# Sheet2.net
KiCad netlist of a schematic drawn in Altium Designer
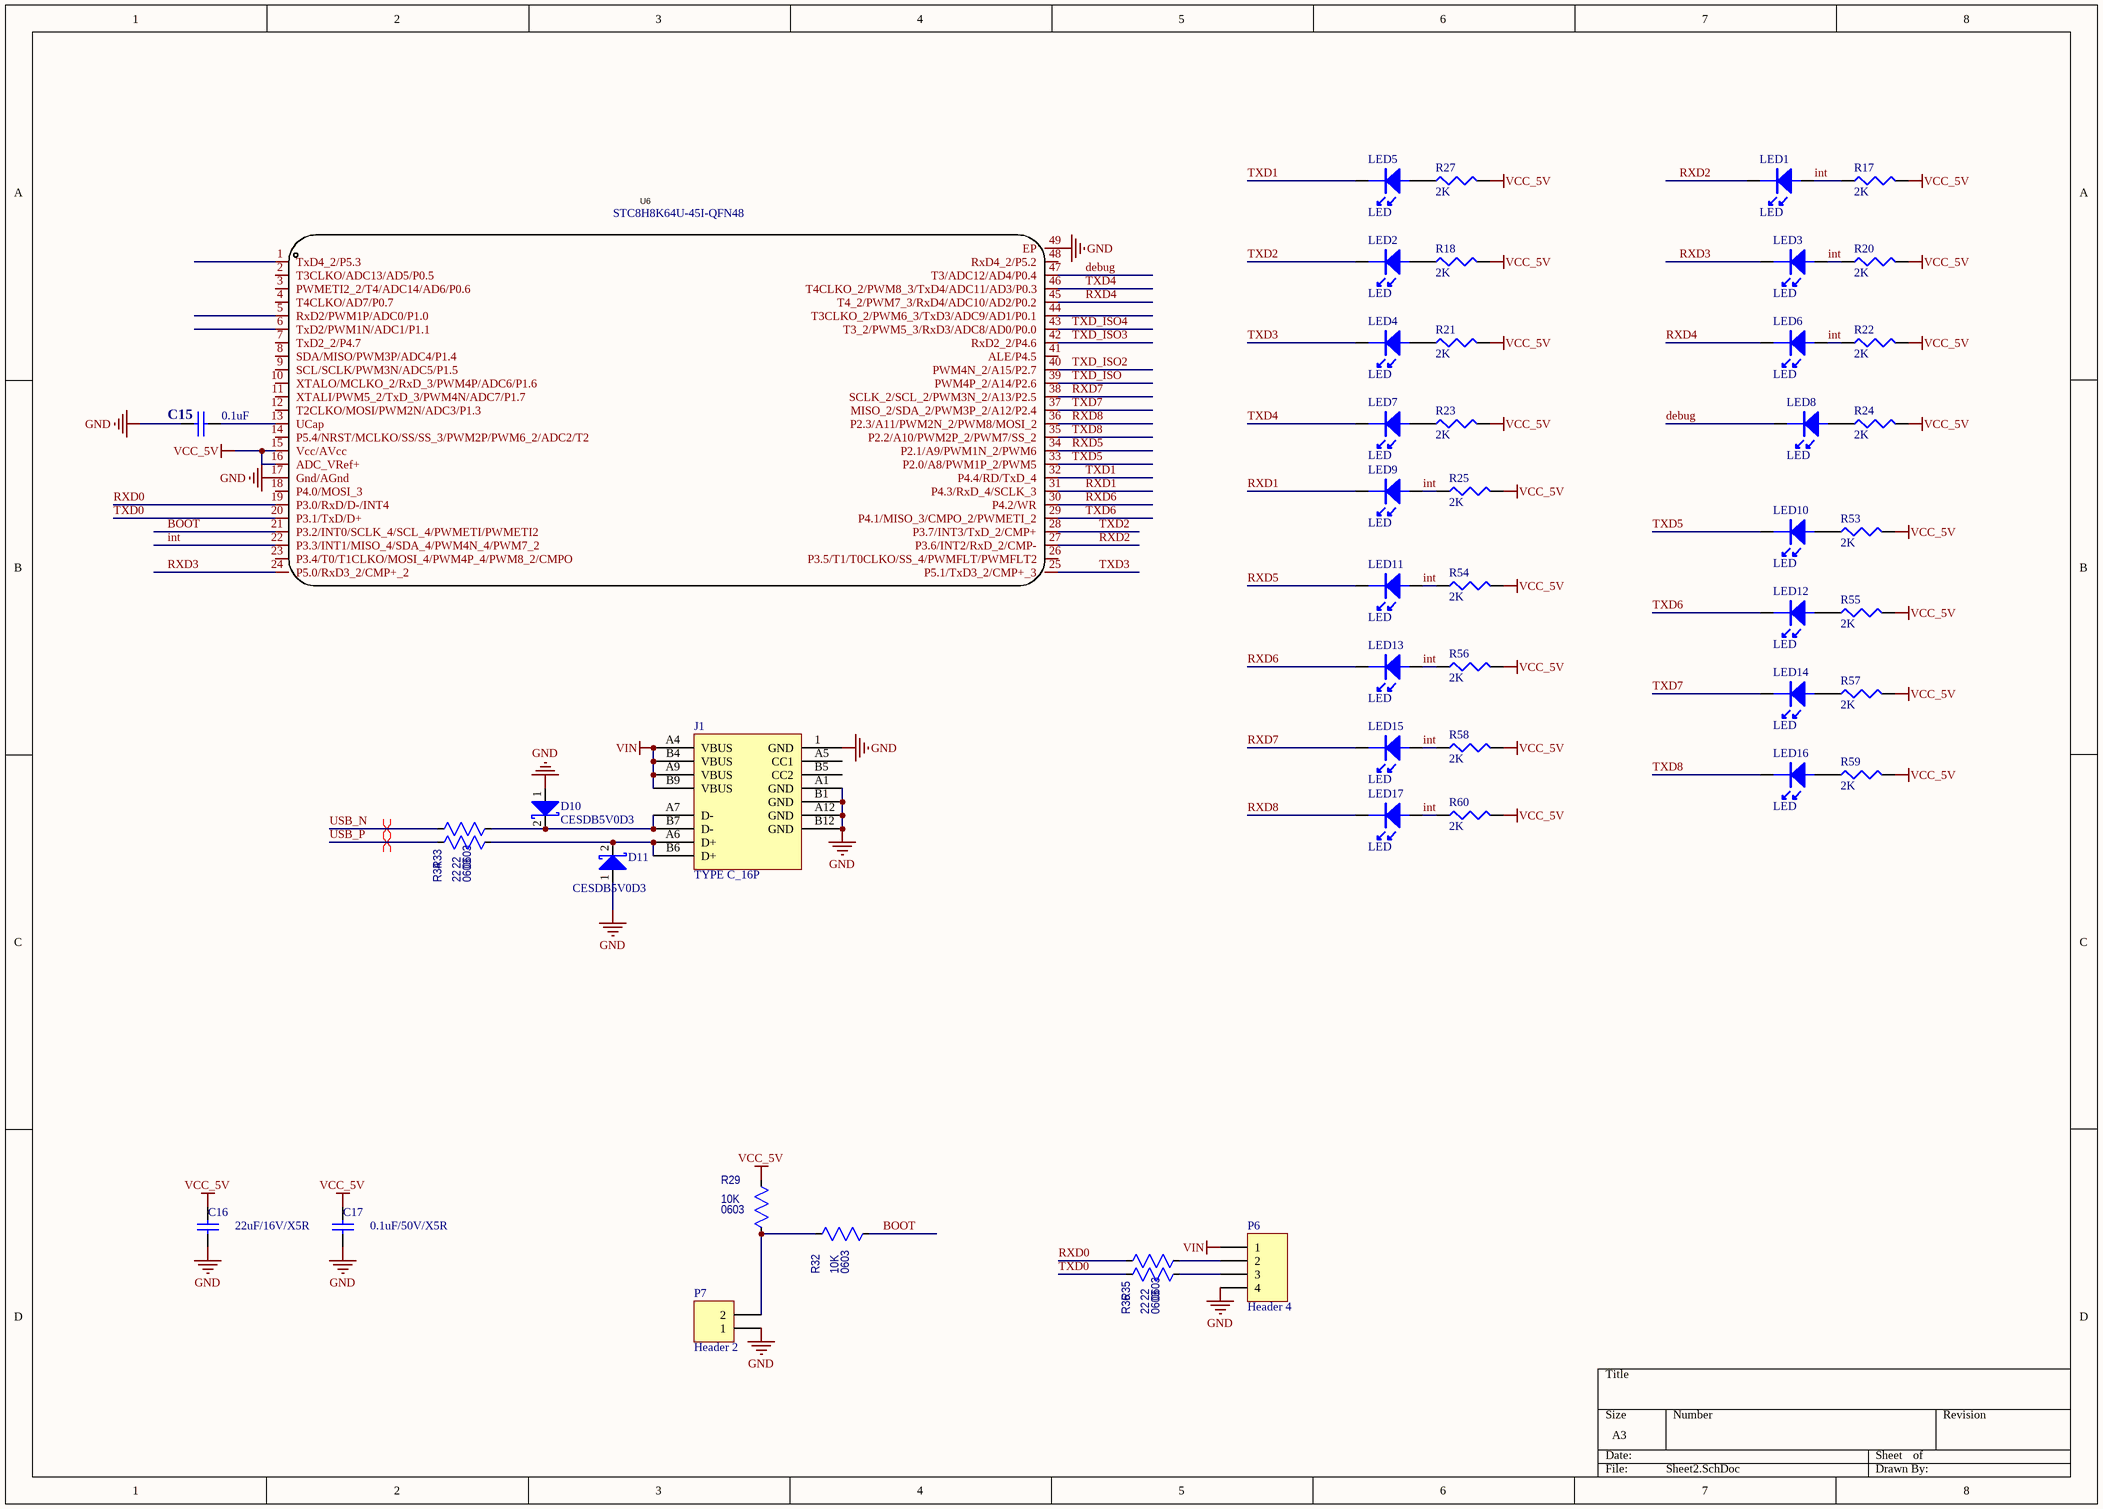
[diagram p0: Sheet2.SchDoc]

(export (version "E")
  (design (tool "Eeschema 10.0.6"))
  (components
    (comp (ref "C15")
      (value "0.1uF")
      (footprint "0603C")
      (description "Capacitor")
      (libsource (lib "*") (part "CAP"))
    )
    (comp (ref "C16")
      (value "22uF/16V/X5R")
      (footprint "0805C")
      (description "贴片电容 20%")
      (libsource (lib "XiaoyI") (part "CAP4"))
    )
    (comp (ref "C17")
      (value "0.1uF/50V/X5R")
      (footprint "0603C")
      (description "贴片电容 20%")
      (libsource (lib "XiaoyI") (part "CAP4"))
    )
    (comp (ref "D10")
      (value "CESDB5V0D3")
      (footprint "SOD323")
      (description "Schottky Diode")
      (libsource (lib "*") (part "DIODE S"))
    )
    (comp (ref "D11")
      (value "CESDB5V0D3")
      (footprint "SOD323")
      (description "Schottky Diode")
      (libsource (lib "*") (part "DIODE S"))
    )
    (comp (ref "J1")
      (value "TYPE C_16P")
      (footprint "TYPEC_16P")
      (libsource (lib "Schlib_20110825") (part "TYPE C_16P"))
    )
    (comp (ref "LED1") (value "LED") (footprint "0603LED") (libsource (lib "我的元件库") (part "LED")))
    (comp (ref "LED2") (value "LED") (footprint "0603LED") (libsource (lib "我的元件库") (part "LED")))
    (comp (ref "LED3") (value "LED") (footprint "0603LED") (libsource (lib "我的元件库") (part "LED")))
    (comp (ref "LED4") (value "LED") (footprint "0603LED") (libsource (lib "我的元件库") (part "LED")))
    (comp (ref "LED5") (value "LED") (footprint "0603LED") (libsource (lib "我的元件库") (part "LED")))
    (comp (ref "LED6") (value "LED") (footprint "0603LED") (libsource (lib "我的元件库") (part "LED")))
    (comp (ref "LED7") (value "LED") (footprint "0603LED") (libsource (lib "我的元件库") (part "LED")))
    (comp (ref "LED8") (value "LED") (footprint "0603LED") (libsource (lib "我的元件库") (part "LED")))
    (comp (ref "LED9") (value "LED") (footprint "0603LED") (libsource (lib "我的元件库") (part "LED")))
    (comp (ref "LED10") (value "LED") (footprint "0603LED") (libsource (lib "我的元件库") (part "LED")))
    (comp (ref "LED11") (value "LED") (footprint "0603LED") (libsource (lib "我的元件库") (part "LED")))
    (comp (ref "LED12") (value "LED") (footprint "0603LED") (libsource (lib "我的元件库") (part "LED")))
    (comp (ref "LED13") (value "LED") (footprint "0603LED") (libsource (lib "我的元件库") (part "LED")))
    (comp (ref "LED14") (value "LED") (footprint "0603LED") (libsource (lib "我的元件库") (part "LED")))
    (comp (ref "LED15") (value "LED") (footprint "0603LED") (libsource (lib "我的元件库") (part "LED")))
    (comp (ref "LED16") (value "LED") (footprint "0603LED") (libsource (lib "我的元件库") (part "LED")))
    (comp (ref "LED17") (value "LED") (footprint "0603LED") (libsource (lib "我的元件库") (part "LED")))
    (comp (ref "P6")
      (value "Header 4")
      (footprint "HDR1X4")
      (description "Header, 4-Pin")
      (fields (field (name "PUBLISHER") "Altium Limited"))
      (libsource (lib "Miscellaneous Connectors") (part "Header 4"))
    )
    (comp (ref "P7")
      (value "Header 2")
      (footprint "HDR1X2")
      (description "Header, 2-Pin")
      (fields (field (name "PUBLISHER") "Altium Limited"))
      (libsource (lib "Miscellaneous Connectors") (part "Header 2"))
    )
    (comp (ref "R17")
      (value "2K")
      (footprint "0603R")
      (libsource (lib "ZWLIntegrated_Library") (part "RES1"))
    )
    (comp (ref "R18")
      (value "2K")
      (footprint "0603R")
      (libsource (lib "ZWLIntegrated_Library") (part "RES1"))
    )
    (comp (ref "R20")
      (value "2K")
      (footprint "0603R")
      (libsource (lib "ZWLIntegrated_Library") (part "RES1"))
    )
    (comp (ref "R21")
      (value "2K")
      (footprint "0603R")
      (libsource (lib "ZWLIntegrated_Library") (part "RES1"))
    )
    (comp (ref "R22")
      (value "2K")
      (footprint "0603R")
      (libsource (lib "ZWLIntegrated_Library") (part "RES1"))
    )
    (comp (ref "R23")
      (value "2K")
      (footprint "0603R")
      (libsource (lib "ZWLIntegrated_Library") (part "RES1"))
    )
    (comp (ref "R24")
      (value "2K")
      (footprint "0603R")
      (libsource (lib "ZWLIntegrated_Library") (part "RES1"))
    )
    (comp (ref "R25")
      (value "2K")
      (footprint "0603R")
      (libsource (lib "ZWLIntegrated_Library") (part "RES1"))
    )
    (comp (ref "R27")
      (value "2K")
      (footprint "0603R")
      (libsource (lib "ZWLIntegrated_Library") (part "RES1"))
    )
    (comp (ref "R29")
      (value "10K")
      (footprint "0603r")
      (fields
        (field (name "PARTNUMBER") "RC0603FR-071KL")
        (field (name "TOLERANCE") "tol")
        (field (name "PACKAGE") "0603")
        (field (name "Comment") "10k")
      )
      (libsource (lib "Karl") (part "Resistor_0603"))
    )
    (comp (ref "R32")
      (value "10K")
      (footprint "0603r")
      (fields
        (field (name "PARTNUMBER") "RC0603FR-071KL")
        (field (name "TOLERANCE") "tol")
        (field (name "PACKAGE") "0603")
        (field (name "Comment") "10k")
      )
      (libsource (lib "Karl") (part "Resistor_0603"))
    )
    (comp (ref "R33")
      (value "22")
      (footprint "0603r")
      (fields
        (field (name "PARTNUMBER") "RC0603FR-071KL")
        (field (name "TOLERANCE") "tol")
        (field (name "PACKAGE") "0603")
        (field (name "Comment") "10k")
      )
      (libsource (lib "Karl") (part "Resistor_0603"))
    )
    (comp (ref "R34")
      (value "22")
      (footprint "0603r")
      (fields
        (field (name "PARTNUMBER") "RC0603FR-071KL")
        (field (name "TOLERANCE") "tol")
        (field (name "PACKAGE") "0603")
        (field (name "Comment") "10k")
      )
      (libsource (lib "Karl") (part "Resistor_0603"))
    )
    (comp (ref "R35")
      (value "22")
      (footprint "0603r")
      (fields
        (field (name "PARTNUMBER") "RC0603FR-071KL")
        (field (name "TOLERANCE") "tol")
        (field (name "PACKAGE") "0603")
        (field (name "Comment") "10k")
      )
      (libsource (lib "Karl") (part "Resistor_0603"))
    )
    (comp (ref "R36")
      (value "22")
      (footprint "0603r")
      (fields
        (field (name "PARTNUMBER") "RC0603FR-071KL")
        (field (name "TOLERANCE") "tol")
        (field (name "PACKAGE") "0603")
        (field (name "Comment") "10k")
      )
      (libsource (lib "Karl") (part "Resistor_0603"))
    )
    (comp (ref "R53")
      (value "2K")
      (footprint "0603R")
      (libsource (lib "ZWLIntegrated_Library") (part "RES1"))
    )
    (comp (ref "R54")
      (value "2K")
      (footprint "0603R")
      (libsource (lib "ZWLIntegrated_Library") (part "RES1"))
    )
    (comp (ref "R55")
      (value "2K")
      (footprint "0603R")
      (libsource (lib "ZWLIntegrated_Library") (part "RES1"))
    )
    (comp (ref "R56")
      (value "2K")
      (footprint "0603R")
      (libsource (lib "ZWLIntegrated_Library") (part "RES1"))
    )
    (comp (ref "R57")
      (value "2K")
      (footprint "0603R")
      (libsource (lib "ZWLIntegrated_Library") (part "RES1"))
    )
    (comp (ref "R58")
      (value "2K")
      (footprint "0603R")
      (libsource (lib "ZWLIntegrated_Library") (part "RES1"))
    )
    (comp (ref "R59")
      (value "2K")
      (footprint "0603R")
      (libsource (lib "ZWLIntegrated_Library") (part "RES1"))
    )
    (comp (ref "R60")
      (value "2K")
      (footprint "0603R")
      (libsource (lib "ZWLIntegrated_Library") (part "RES1"))
    )
    (comp (ref "U6")
      (value "STC8H8K64U-45I-QFN48")
      (footprint "QFN-48_L6.0-W6.0-P0.40-TL-EP4.4")
      (libsource (lib "altium-import") (part "root_0_STC8H8K64U-45I-QFN48_"))
    )
  )
  (nets
    (net (code "1") (name "/BOOT") (class "Default")
      (node (ref "R32") (pin "2") (pinfunction "2_2") (pintype "passive"))
      (node (ref "U6") (pin "21") (pinfunction "P3.2/INT0/SCLK_4/SCL_4/PWMETI/PWMETI2_21") (pintype "passive"))
    )
    (net (code "2") (name "/RXD0") (class "Default")
      (node (ref "R35") (pin "1") (pinfunction "1_1") (pintype "passive"))
      (node (ref "U6") (pin "19") (pinfunction "P3.0/RxD/D-/INT4_19") (pintype "passive"))
    )
    (net (code "3") (name "/RXD1") (class "Default")
      (node (ref "LED9") (pin "2") (pinfunction "2_2") (pintype "passive"))
      (node (ref "U6") (pin "31") (pinfunction "P4.3/RxD_4/SCLK_3_31") (pintype "passive"))
    )
    (net (code "4") (name "/RXD2") (class "Default")
      (node (ref "LED1") (pin "2") (pinfunction "2_2") (pintype "passive"))
      (node (ref "U6") (pin "27") (pinfunction "P3.6/INT2/RxD_2/CMP-_27") (pintype "passive"))
    )
    (net (code "5") (name "/RXD3") (class "Default")
      (node (ref "LED3") (pin "2") (pinfunction "2_2") (pintype "passive"))
      (node (ref "U6") (pin "24") (pinfunction "P5.0/RxD3_2/CMP+_2_24") (pintype "passive"))
    )
    (net (code "6") (name "/RXD4") (class "Default")
      (node (ref "LED6") (pin "2") (pinfunction "2_2") (pintype "passive"))
      (node (ref "U6") (pin "45") (pinfunction "T4_2/PWM7_3/RxD4/ADC10/AD2/P0.2_45") (pintype "passive"))
    )
    (net (code "7") (name "/RXD5") (class "Default")
      (node (ref "LED11") (pin "2") (pinfunction "2_2") (pintype "passive"))
      (node (ref "U6") (pin "34") (pinfunction "P2.1/A9/PWM1N_2/PWM6_34") (pintype "passive"))
    )
    (net (code "8") (name "/RXD6") (class "Default")
      (node (ref "LED13") (pin "2") (pinfunction "2_2") (pintype "passive"))
      (node (ref "U6") (pin "30") (pinfunction "P4.2/WR_30") (pintype "passive"))
    )
    (net (code "9") (name "/RXD7") (class "Default")
      (node (ref "LED15") (pin "2") (pinfunction "2_2") (pintype "passive"))
      (node (ref "U6") (pin "38") (pinfunction "SCLK_2/SCL_2/PWM3N_2/A13/P2.5_38") (pintype "passive"))
    )
    (net (code "10") (name "/RXD8") (class "Default")
      (node (ref "LED17") (pin "2") (pinfunction "2_2") (pintype "passive"))
      (node (ref "U6") (pin "36") (pinfunction "P2.3/A11/PWM2N_2/PWM8/MOSI_2_36") (pintype "passive"))
    )
    (net (code "11") (name "/TXD0") (class "Default")
      (node (ref "R36") (pin "1") (pinfunction "1_1") (pintype "passive"))
      (node (ref "U6") (pin "20") (pinfunction "P3.1/TxD/D+_20") (pintype "passive"))
    )
    (net (code "12") (name "/TXD1") (class "Default")
      (node (ref "LED5") (pin "2") (pinfunction "2_2") (pintype "passive"))
      (node (ref "U6") (pin "32") (pinfunction "P4.4/RD/TxD_4_32") (pintype "passive"))
    )
    (net (code "13") (name "/TXD2") (class "Default")
      (node (ref "LED2") (pin "2") (pinfunction "2_2") (pintype "passive"))
      (node (ref "U6") (pin "28") (pinfunction "P3.7/INT3/TxD_2/CMP+_28") (pintype "passive"))
    )
    (net (code "14") (name "/TXD3") (class "Default")
      (node (ref "LED4") (pin "2") (pinfunction "2_2") (pintype "passive"))
      (node (ref "U6") (pin "25") (pinfunction "P5.1/TxD3_2/CMP+_3_25") (pintype "passive"))
    )
    (net (code "15") (name "/TXD4") (class "Default")
      (node (ref "LED7") (pin "2") (pinfunction "2_2") (pintype "passive"))
      (node (ref "U6") (pin "46") (pinfunction "T4CLKO_2/PWM8_3/TxD4/ADC11/AD3/P0.3_46") (pintype "passive"))
    )
    (net (code "16") (name "/TXD5") (class "Default")
      (node (ref "LED10") (pin "2") (pinfunction "2_2") (pintype "passive"))
      (node (ref "U6") (pin "33") (pinfunction "P2.0/A8/PWM1P_2/PWM5_33") (pintype "passive"))
    )
    (net (code "17") (name "/TXD6") (class "Default")
      (node (ref "LED12") (pin "2") (pinfunction "2_2") (pintype "passive"))
      (node (ref "U6") (pin "29") (pinfunction "P4.1/MISO_3/CMPO_2/PWMETI_2_29") (pintype "passive"))
    )
    (net (code "18") (name "/TXD7") (class "Default")
      (node (ref "LED14") (pin "2") (pinfunction "2_2") (pintype "passive"))
      (node (ref "U6") (pin "37") (pinfunction "MISO_2/SDA_2/PWM3P_2/A12/P2.4_37") (pintype "passive"))
    )
    (net (code "19") (name "/TXD8") (class "Default")
      (node (ref "LED16") (pin "2") (pinfunction "2_2") (pintype "passive"))
      (node (ref "U6") (pin "35") (pinfunction "P2.2/A10/PWM2P_2/PWM7/SS_2_35") (pintype "passive"))
    )
    (net (code "20") (name "/TXD_ISO") (class "Default")
      (node (ref "U6") (pin "39") (pinfunction "PWM4P_2/A14/P2.6_39") (pintype "passive"))
    )
    (net (code "21") (name "/TXD_ISO2") (class "Default")
      (node (ref "U6") (pin "40") (pinfunction "PWM4N_2/A15/P2.7_40") (pintype "passive"))
    )
    (net (code "22") (name "/TXD_ISO3") (class "Default")
      (node (ref "U6") (pin "42") (pinfunction "RxD2_2/P4.6_42") (pintype "passive"))
    )
    (net (code "23") (name "/TXD_ISO4") (class "Default")
      (node (ref "U6") (pin "43") (pinfunction "T3_2/PWM5_3/RxD3/ADC8/AD0/P0.0_43") (pintype "passive"))
    )
    (net (code "24") (name "/USB_N") (class "Default")
      (node (ref "R33") (pin "1") (pinfunction "1_1") (pintype "passive"))
    )
    (net (code "25") (name "/USB_P") (class "Default")
      (node (ref "R34") (pin "1") (pinfunction "1_1") (pintype "passive"))
    )
    (net (code "26") (name "/debug") (class "Default")
      (node (ref "LED8") (pin "2") (pinfunction "2_2") (pintype "passive"))
      (node (ref "U6") (pin "47") (pinfunction "T3/ADC12/AD4/P0.4_47") (pintype "passive"))
    )
    (net (code "27") (name "/int") (class "Default")
      (node (ref "LED1") (pin "1") (pinfunction "1_1") (pintype "passive"))
      (node (ref "LED11") (pin "1") (pinfunction "1_1") (pintype "passive"))
      (node (ref "LED13") (pin "1") (pinfunction "1_1") (pintype "passive"))
      (node (ref "LED15") (pin "1") (pinfunction "1_1") (pintype "passive"))
      (node (ref "LED17") (pin "1") (pinfunction "1_1") (pintype "passive"))
      (node (ref "LED3") (pin "1") (pinfunction "1_1") (pintype "passive"))
      (node (ref "LED6") (pin "1") (pinfunction "1_1") (pintype "passive"))
      (node (ref "LED9") (pin "1") (pinfunction "1_1") (pintype "passive"))
      (node (ref "R17") (pin "1") (pinfunction "1_1") (pintype "passive"))
      (node (ref "R20") (pin "1") (pinfunction "1_1") (pintype "passive"))
      (node (ref "R22") (pin "1") (pinfunction "1_1") (pintype "passive"))
      (node (ref "R25") (pin "1") (pinfunction "1_1") (pintype "passive"))
      (node (ref "R54") (pin "1") (pinfunction "1_1") (pintype "passive"))
      (node (ref "R56") (pin "1") (pinfunction "1_1") (pintype "passive"))
      (node (ref "R58") (pin "1") (pinfunction "1_1") (pintype "passive"))
      (node (ref "R60") (pin "1") (pinfunction "1_1") (pintype "passive"))
      (node (ref "U6") (pin "22") (pinfunction "P3.3/INT1/MISO_4/SDA_4/PWM4N_4/PWM7_2_22") (pintype "passive"))
    )
    (net (code "28") (name "GND") (class "Default")
      (node (ref "C15") (pin "1") (pinfunction "1_1") (pintype "passive"))
      (node (ref "C16") (pin "1") (pinfunction "1_1") (pintype "passive"))
      (node (ref "C17") (pin "1") (pinfunction "1_1") (pintype "passive"))
      (node (ref "D10") (pin "1") (pinfunction "A_1") (pintype "passive"))
      (node (ref "D11") (pin "1") (pinfunction "A_1") (pintype "passive"))
      (node (ref "J1") (pin "1") (pinfunction "GND_1") (pintype "passive"))
      (node (ref "J1") (pin "A1") (pinfunction "GND_A1") (pintype "passive"))
      (node (ref "J1") (pin "A12") (pinfunction "GND_A12") (pintype "passive"))
      (node (ref "J1") (pin "B1") (pinfunction "GND_B1") (pintype "passive"))
      (node (ref "J1") (pin "B12") (pinfunction "GND_B12") (pintype "passive"))
      (node (ref "P6") (pin "4") (pinfunction "4_4") (pintype "passive"))
      (node (ref "P7") (pin "1") (pinfunction "1_1") (pintype "passive"))
      (node (ref "U6") (pin "17") (pinfunction "Gnd/AGnd_17") (pintype "passive"))
      (node (ref "U6") (pin "49") (pinfunction "EP_49") (pintype "passive"))
    )
    (net (code "29") (name "Net-(D10-K)") (class "Default")
      (node (ref "D10") (pin "2") (pinfunction "K_2") (pintype "passive"))
      (node (ref "J1") (pin "A7") (pinfunction "D-_A7") (pintype "passive"))
      (node (ref "J1") (pin "B7") (pinfunction "D-_B7") (pintype "passive"))
      (node (ref "R33") (pin "2") (pinfunction "2_2") (pintype "passive"))
    )
    (net (code "30") (name "Net-(D11-K)") (class "Default")
      (node (ref "D11") (pin "2") (pinfunction "K_2") (pintype "passive"))
      (node (ref "J1") (pin "A6") (pinfunction "D+_A6") (pintype "passive"))
      (node (ref "J1") (pin "B6") (pinfunction "D+_B6") (pintype "passive"))
      (node (ref "R34") (pin "2") (pinfunction "2_2") (pintype "passive"))
    )
    (net (code "31") (name "Net-(LED2-Pad1)") (class "Default")
      (node (ref "LED2") (pin "1") (pinfunction "1_1") (pintype "passive"))
      (node (ref "R18") (pin "1") (pinfunction "1_1") (pintype "passive"))
    )
    (net (code "32") (name "Net-(LED4-Pad1)") (class "Default")
      (node (ref "LED4") (pin "1") (pinfunction "1_1") (pintype "passive"))
      (node (ref "R21") (pin "1") (pinfunction "1_1") (pintype "passive"))
    )
    (net (code "33") (name "Net-(LED5-Pad1)") (class "Default")
      (node (ref "LED5") (pin "1") (pinfunction "1_1") (pintype "passive"))
      (node (ref "R27") (pin "1") (pinfunction "1_1") (pintype "passive"))
    )
    (net (code "34") (name "Net-(LED7-Pad1)") (class "Default")
      (node (ref "LED7") (pin "1") (pinfunction "1_1") (pintype "passive"))
      (node (ref "R23") (pin "1") (pinfunction "1_1") (pintype "passive"))
    )
    (net (code "35") (name "Net-(LED8-Pad1)") (class "Default")
      (node (ref "LED8") (pin "1") (pinfunction "1_1") (pintype "passive"))
      (node (ref "R24") (pin "1") (pinfunction "1_1") (pintype "passive"))
    )
    (net (code "36") (name "Net-(LED10-Pad1)") (class "Default")
      (node (ref "LED10") (pin "1") (pinfunction "1_1") (pintype "passive"))
      (node (ref "R53") (pin "1") (pinfunction "1_1") (pintype "passive"))
    )
    (net (code "37") (name "Net-(LED12-Pad1)") (class "Default")
      (node (ref "LED12") (pin "1") (pinfunction "1_1") (pintype "passive"))
      (node (ref "R55") (pin "1") (pinfunction "1_1") (pintype "passive"))
    )
    (net (code "38") (name "Net-(LED14-Pad1)") (class "Default")
      (node (ref "LED14") (pin "1") (pinfunction "1_1") (pintype "passive"))
      (node (ref "R57") (pin "1") (pinfunction "1_1") (pintype "passive"))
    )
    (net (code "39") (name "Net-(LED16-Pad1)") (class "Default")
      (node (ref "LED16") (pin "1") (pinfunction "1_1") (pintype "passive"))
      (node (ref "R59") (pin "1") (pinfunction "1_1") (pintype "passive"))
    )
    (net (code "40") (name "Net-(P6-Pad2)") (class "Default")
      (node (ref "P6") (pin "2") (pinfunction "2_2") (pintype "passive"))
      (node (ref "R35") (pin "2") (pinfunction "2_2") (pintype "passive"))
    )
    (net (code "41") (name "Net-(P6-Pad3)") (class "Default")
      (node (ref "P6") (pin "3") (pinfunction "3_3") (pintype "passive"))
      (node (ref "R36") (pin "2") (pinfunction "2_2") (pintype "passive"))
    )
    (net (code "42") (name "Net-(P7-Pad2)") (class "Default")
      (node (ref "P7") (pin "2") (pinfunction "2_2") (pintype "passive"))
      (node (ref "R29") (pin "2") (pinfunction "2_2") (pintype "passive"))
      (node (ref "R32") (pin "1") (pinfunction "1_1") (pintype "passive"))
    )
    (net (code "43") (name "Net-(U6-UCap)") (class "Default")
      (node (ref "C15") (pin "2") (pinfunction "2_2") (pintype "passive"))
      (node (ref "U6") (pin "13") (pinfunction "UCap_13") (pintype "passive"))
    )
    (net (code "44") (name "VCC_5V") (class "Default")
      (node (ref "C16") (pin "2") (pinfunction "2_2") (pintype "passive"))
      (node (ref "C17") (pin "2") (pinfunction "2_2") (pintype "passive"))
      (node (ref "R17") (pin "2") (pinfunction "2_2") (pintype "passive"))
      (node (ref "R18") (pin "2") (pinfunction "2_2") (pintype "passive"))
      (node (ref "R20") (pin "2") (pinfunction "2_2") (pintype "passive"))
      (node (ref "R21") (pin "2") (pinfunction "2_2") (pintype "passive"))
      (node (ref "R22") (pin "2") (pinfunction "2_2") (pintype "passive"))
      (node (ref "R23") (pin "2") (pinfunction "2_2") (pintype "passive"))
      (node (ref "R24") (pin "2") (pinfunction "2_2") (pintype "passive"))
      (node (ref "R25") (pin "2") (pinfunction "2_2") (pintype "passive"))
      (node (ref "R27") (pin "2") (pinfunction "2_2") (pintype "passive"))
      (node (ref "R29") (pin "1") (pinfunction "1_1") (pintype "passive"))
      (node (ref "R53") (pin "2") (pinfunction "2_2") (pintype "passive"))
      (node (ref "R54") (pin "2") (pinfunction "2_2") (pintype "passive"))
      (node (ref "R55") (pin "2") (pinfunction "2_2") (pintype "passive"))
      (node (ref "R56") (pin "2") (pinfunction "2_2") (pintype "passive"))
      (node (ref "R57") (pin "2") (pinfunction "2_2") (pintype "passive"))
      (node (ref "R58") (pin "2") (pinfunction "2_2") (pintype "passive"))
      (node (ref "R59") (pin "2") (pinfunction "2_2") (pintype "passive"))
      (node (ref "R60") (pin "2") (pinfunction "2_2") (pintype "passive"))
      (node (ref "U6") (pin "15") (pinfunction "Vcc/AVcc_15") (pintype "passive"))
      (node (ref "U6") (pin "16") (pinfunction "ADC_VRef+_16") (pintype "passive"))
    )
    (net (code "45") (name "VIN") (class "Default")
      (node (ref "J1") (pin "A4") (pinfunction "VBUS_A4") (pintype "passive"))
      (node (ref "J1") (pin "A9") (pinfunction "VBUS_A9") (pintype "passive"))
      (node (ref "J1") (pin "B4") (pinfunction "VBUS_B4") (pintype "passive"))
      (node (ref "J1") (pin "B9") (pinfunction "VBUS_B9") (pintype "passive"))
      (node (ref "P6") (pin "1") (pinfunction "1_1") (pintype "passive"))
    )
    (net (code "46") (name "unconnected-(J1-CC1-PadA5)") (class "Default")
      (node (ref "J1") (pin "A5") (pinfunction "CC1_A5") (pintype "passive"))
    )
    (net (code "47") (name "unconnected-(J1-CC2-PadB5)") (class "Default")
      (node (ref "J1") (pin "B5") (pinfunction "CC2_B5") (pintype "passive"))
    )
    (net (code "48") (name "unconnected-(U6-ALE{slash}P4.5-Pad41)") (class "Default")
      (node (ref "U6") (pin "41") (pinfunction "ALE/P4.5_41") (pintype "passive"))
    )
    (net (code "49") (name "unconnected-(U6-P3.4{slash}T0{slash}T1CLKO{slash}MOSI_4{slash}PWM4P_4{slash}PWM8_2{slash}CMPO-Pad23)") (class "Default")
      (node (ref "U6") (pin "23") (pinfunction "P3.4/T0/T1CLKO/MOSI_4/PWM4P_4/PWM8_2/CMPO_23") (pintype "passive"))
    )
    (net (code "50") (name "unconnected-(U6-P3.5{slash}T1{slash}T0CLKO{slash}SS_4{slash}PWMFLT{slash}PWMFLT2-Pad26)") (class "Default")
      (node (ref "U6") (pin "26") (pinfunction "P3.5/T1/T0CLKO/SS_4/PWMFLT/PWMFLT2_26") (pintype "passive"))
    )
    (net (code "51") (name "unconnected-(U6-P4.0{slash}MOSI_3-Pad18)") (class "Default")
      (node (ref "U6") (pin "18") (pinfunction "P4.0/MOSI_3_18") (pintype "passive"))
    )
    (net (code "52") (name "unconnected-(U6-P5.4{slash}NRST{slash}MCLKO{slash}SS{slash}SS_3{slash}PWM2P{slash}PWM6_2{slash}ADC2{slash}T2-Pad14)") (class "Default")
      (node (ref "U6") (pin "14") (pinfunction "P5.4/NRST/MCLKO/SS/SS_3/PWM2P/PWM6_2/ADC2/T2_14") (pintype "passive"))
    )
    (net (code "53") (name "unconnected-(U6-PWMETI2_2{slash}T4{slash}ADC14{slash}AD6{slash}P0.6-Pad3)") (class "Default")
      (node (ref "U6") (pin "3") (pinfunction "PWMETI2_2/T4/ADC14/AD6/P0.6_3") (pintype "passive"))
    )
    (net (code "54") (name "unconnected-(U6-RxD2{slash}PWM1P{slash}ADC0{slash}P1.0-Pad5)") (class "Default")
      (node (ref "U6") (pin "5") (pinfunction "RxD2/PWM1P/ADC0/P1.0_5") (pintype "passive"))
    )
    (net (code "55") (name "unconnected-(U6-RxD4_2{slash}P5.2-Pad48)") (class "Default")
      (node (ref "U6") (pin "48") (pinfunction "RxD4_2/P5.2_48") (pintype "passive"))
    )
    (net (code "56") (name "unconnected-(U6-SCL{slash}SCLK{slash}PWM3N{slash}ADC5{slash}P1.5-Pad9)") (class "Default")
      (node (ref "U6") (pin "9") (pinfunction "SCL/SCLK/PWM3N/ADC5/P1.5_9") (pintype "passive"))
    )
    (net (code "57") (name "unconnected-(U6-SDA{slash}MISO{slash}PWM3P{slash}ADC4{slash}P1.4-Pad8)") (class "Default")
      (node (ref "U6") (pin "8") (pinfunction "SDA/MISO/PWM3P/ADC4/P1.4_8") (pintype "passive"))
    )
    (net (code "58") (name "unconnected-(U6-T2CLKO{slash}MOSI{slash}PWM2N{slash}ADC3{slash}P1.3-Pad12)") (class "Default")
      (node (ref "U6") (pin "12") (pinfunction "T2CLKO/MOSI/PWM2N/ADC3/P1.3_12") (pintype "passive"))
    )
    (net (code "59") (name "unconnected-(U6-T3CLKO_2{slash}PWM6_3{slash}TxD3{slash}ADC9{slash}AD1{slash}P0.1-Pad44)") (class "Default")
      (node (ref "U6") (pin "44") (pinfunction "T3CLKO_2/PWM6_3/TxD3/ADC9/AD1/P0.1_44") (pintype "passive"))
    )
    (net (code "60") (name "unconnected-(U6-T3CLKO{slash}ADC13{slash}AD5{slash}P0.5-Pad2)") (class "Default")
      (node (ref "U6") (pin "2") (pinfunction "T3CLKO/ADC13/AD5/P0.5_2") (pintype "passive"))
    )
    (net (code "61") (name "unconnected-(U6-T4CLKO{slash}AD7{slash}P0.7-Pad4)") (class "Default")
      (node (ref "U6") (pin "4") (pinfunction "T4CLKO/AD7/P0.7_4") (pintype "passive"))
    )
    (net (code "62") (name "unconnected-(U6-TxD2_2{slash}P4.7-Pad7)") (class "Default")
      (node (ref "U6") (pin "7") (pinfunction "TxD2_2/P4.7_7") (pintype "passive"))
    )
    (net (code "63") (name "unconnected-(U6-TxD2{slash}PWM1N{slash}ADC1{slash}P1.1-Pad6)") (class "Default")
      (node (ref "U6") (pin "6") (pinfunction "TxD2/PWM1N/ADC1/P1.1_6") (pintype "passive"))
    )
    (net (code "64") (name "unconnected-(U6-TxD4_2{slash}P5.3-Pad1)") (class "Default")
      (node (ref "U6") (pin "1") (pinfunction "TxD4_2/P5.3_1") (pintype "passive"))
    )
    (net (code "65") (name "unconnected-(U6-XTALI{slash}PWM5_2{slash}TxD_3{slash}PWM4N{slash}ADC7{slash}P1.7-Pad11)") (class "Default")
      (node (ref "U6") (pin "11") (pinfunction "XTALI/PWM5_2/TxD_3/PWM4N/ADC7/P1.7_11") (pintype "passive"))
    )
    (net (code "66") (name "unconnected-(U6-XTALO{slash}MCLKO_2{slash}RxD_3{slash}PWM4P{slash}ADC6{slash}P1.6-Pad10)") (class "Default")
      (node (ref "U6") (pin "10") (pinfunction "XTALO/MCLKO_2/RxD_3/PWM4P/ADC6/P1.6_10") (pintype "passive"))
    )
  )
)
